# uMultimeter_ExpProbeB_Sch.net
KiCad netlist of a schematic drawn in Altium Designer
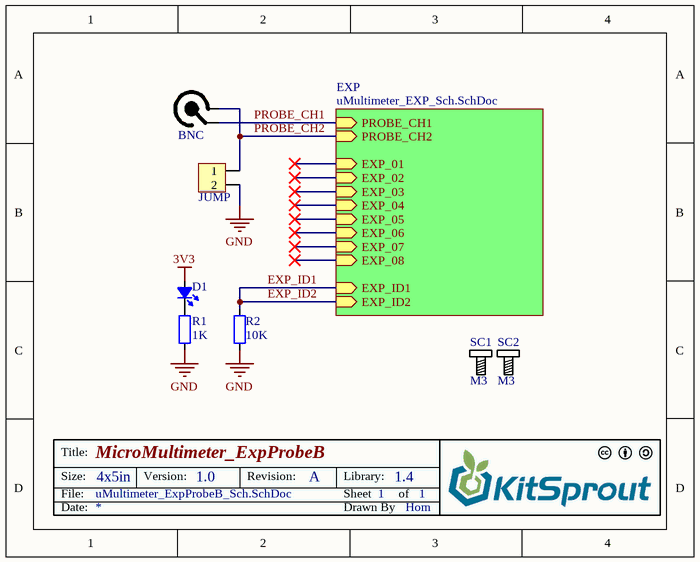
[diagram p0: uMultimeter_ExpProbeB_Sch.SchDoc]

(export (version "E")
  (design (tool "Eeschema 10.0.6"))
  (components
    (comp (ref "BNC")
      (value "BNC")
      (footprint "PCB_ConnectorCable:BNC_4P")
      (libsource (lib "SCH_Connector") (part "BNC"))
    )
    (comp (ref "D1")
      (value "LED_0805")
      (footprint "PCB_ActiveLED:LED_0805_BLUE")
      (description "LED")
      (libsource (lib "SCH_Active") (part "LED_0805"))
    )
    (comp (ref "JUMP")
      (value "HDR1x2_2.54")
      (footprint "PCB_ConnectorHDR:HDR1X2_2.54_180")
      (description "Header")
      (libsource (lib "SCH_ConnectorHDR") (part "HDR1x2_2.54T"))
    )
    (comp (ref "R1")
      (value "1K")
      (footprint "PCB_PassiveRes:RES_0603")
      (description "Resistor")
      (fields (field (name "Comment") "Res_0603"))
      (libsource (lib "SCH_Passive") (part "Res_0603"))
    )
    (comp (ref "R2")
      (value "10K")
      (footprint "PCB_PassiveRes:RES_0603")
      (description "Resistor")
      (fields (field (name "Comment") "Res_0603"))
      (libsource (lib "") (part "Res_0603_1"))
    )
    (comp (ref "SC1")
      (value "M3")
      (footprint "PCB_Mechanical:SCRREW_M3")
      (description "Screw")
      (libsource (lib "SCH_Mechanical") (part "Screw_M3"))
    )
    (comp (ref "SC2")
      (value "M3")
      (footprint "PCB_Mechanical:SCRREW_M3")
      (description "Screw")
      (libsource (lib "SCH_Mechanical") (part "Screw_M3"))
    )
  )
  (nets
    (net (code "9") (name "/EXP_ID1") (class "Default")
      (node (ref "R2") (pin "2") (pinfunction "2_2") (pintype "passive"))
    )
    (net (code "10") (name "/PROBE_CH1") (class "Default")
      (node (ref "BNC") (pin "1") (pinfunction "1_1") (pintype "passive"))
    )
    (net (code "11") (name "/PROBE_CH2") (class "Default")
      (node (ref "BNC") (pin "2") (pinfunction "2_2") (pintype "passive"))
      (node (ref "JUMP") (pin "1") (pinfunction "1_1") (pintype "passive"))
    )
    (net (code "12") (name "3V3") (class "Default")
      (node (ref "D1") (pin "1") (pinfunction "A_1") (pintype "passive"))
    )
    (net (code "13") (name "GND") (class "Default")
      (node (ref "JUMP") (pin "2") (pinfunction "2_2") (pintype "passive"))
      (node (ref "R1") (pin "2") (pinfunction "2_2") (pintype "passive"))
      (node (ref "R2") (pin "1") (pinfunction "1_1") (pintype "passive"))
    )
    (net (code "14") (name "Net-(D1-K)") (class "Default")
      (node (ref "D1") (pin "2") (pinfunction "K_2") (pintype "passive"))
      (node (ref "R1") (pin "1") (pinfunction "1_1") (pintype "passive"))
    )
  )
)
